# SmoothieDriver-DC3.net
KiCad netlist of a schematic drawn in EAGLE
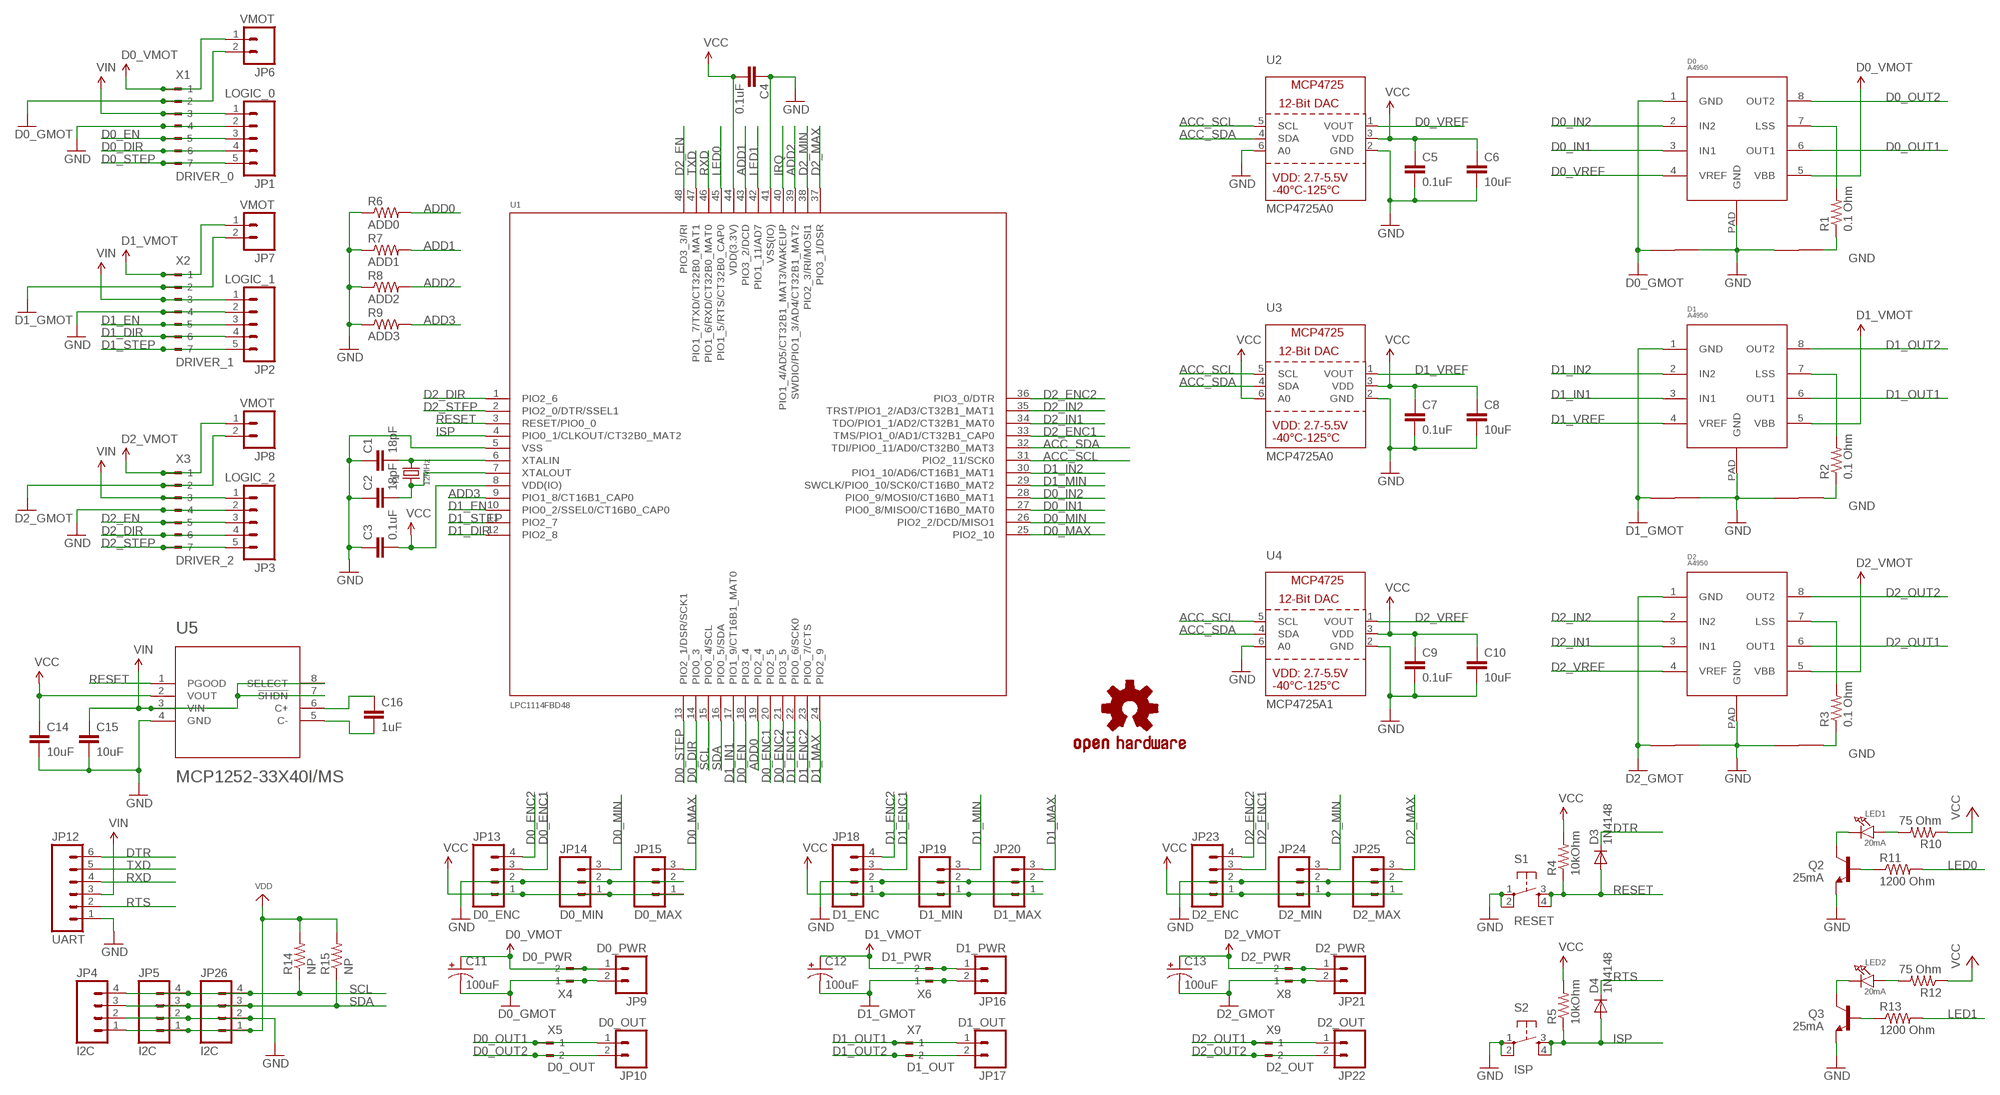
[diagram p0: schematic, sheet 1]

(export (version "E")
  (design (tool "Eeschema 10.0.6"))
  (components
    (comp (ref "C1")
      (value "18pF")
      (footprint "eagle-import:0603-CAP")
      (libsource (lib "eagle-import") (part "CAP0603-CAP"))
    )
    (comp (ref "C2")
      (value "18pF")
      (footprint "eagle-import:0603-CAP")
      (libsource (lib "eagle-import") (part "CAP0603-CAP"))
    )
    (comp (ref "C3")
      (value "0.1uF")
      (footprint "eagle-import:0603-CAP")
      (libsource (lib "eagle-import") (part "CAP0603-CAP"))
    )
    (comp (ref "C4")
      (value "0.1uF")
      (footprint "eagle-import:0603-CAP")
      (libsource (lib "eagle-import") (part "CAP0603-CAP"))
    )
    (comp (ref "C5")
      (value "0.1uF")
      (footprint "eagle-import:0603-CAP")
      (libsource (lib "eagle-import") (part "CAP0603-CAP"))
    )
    (comp (ref "C6")
      (value "10uF")
      (footprint "eagle-import:0603-CAP")
      (libsource (lib "eagle-import") (part "CAP0603-CAP"))
    )
    (comp (ref "C7")
      (value "0.1uF")
      (footprint "eagle-import:0603-CAP")
      (libsource (lib "eagle-import") (part "CAP0603-CAP"))
    )
    (comp (ref "C8")
      (value "10uF")
      (footprint "eagle-import:0603-CAP")
      (libsource (lib "eagle-import") (part "CAP0603-CAP"))
    )
    (comp (ref "C9")
      (value "0.1uF")
      (footprint "eagle-import:0603-CAP")
      (libsource (lib "eagle-import") (part "CAP0603-CAP"))
    )
    (comp (ref "C10")
      (value "10uF")
      (footprint "eagle-import:0603-CAP")
      (libsource (lib "eagle-import") (part "CAP0603-CAP"))
    )
    (comp (ref "C11")
      (value "100uF")
      (footprint "eagle-import:PANASONIC_E")
      (libsource (lib "eagle-import") (part "CAP_POLE"))
    )
    (comp (ref "C12")
      (value "100uF")
      (footprint "eagle-import:PANASONIC_E")
      (libsource (lib "eagle-import") (part "CAP_POLE"))
    )
    (comp (ref "C13")
      (value "100uF")
      (footprint "eagle-import:PANASONIC_E")
      (libsource (lib "eagle-import") (part "CAP_POLE"))
    )
    (comp (ref "C14")
      (value "10uF")
      (footprint "eagle-import:1206")
      (libsource (lib "eagle-import") (part "CAP1206"))
    )
    (comp (ref "C15")
      (value "10uF")
      (footprint "eagle-import:1206")
      (libsource (lib "eagle-import") (part "CAP1206"))
    )
    (comp (ref "C16")
      (value "1uF")
      (footprint "eagle-import:0805")
      (libsource (lib "eagle-import") (part "CAP0805"))
    )
    (comp (ref "D0")
      (value "A4950")
      (footprint "eagle-import:SOICN8-PAD")
      (libsource (lib "eagle-import") (part "A4950"))
    )
    (comp (ref "D0_GMOT")
      (value "NET_LINK")
      (footprint "eagle-import:NET_LINK")
      (libsource (lib "eagle-import") (part "NET_LINK"))
    )
    (comp (ref "D1")
      (value "A4950")
      (footprint "eagle-import:SOICN8-PAD")
      (libsource (lib "eagle-import") (part "A4950"))
    )
    (comp (ref "D2")
      (value "A4950")
      (footprint "eagle-import:SOICN8-PAD")
      (libsource (lib "eagle-import") (part "A4950"))
    )
    (comp (ref "D3")
      (value "1N4148")
      (footprint "eagle-import:SOD523")
      (libsource (lib "eagle-import") (part "DIODESOD523"))
    )
    (comp (ref "D4")
      (value "1N4148")
      (footprint "eagle-import:SOD523")
      (libsource (lib "eagle-import") (part "DIODESOD523"))
    )
    (comp (ref "JP1")
      (value "LOGIC_0")
      (footprint "eagle-import:1X05")
      (libsource (lib "eagle-import") (part "M05PTH"))
    )
    (comp (ref "JP2")
      (value "LOGIC_1")
      (footprint "eagle-import:1X05")
      (libsource (lib "eagle-import") (part "M05PTH"))
    )
    (comp (ref "JP3")
      (value "LOGIC_2")
      (footprint "eagle-import:1X05")
      (libsource (lib "eagle-import") (part "M05PTH"))
    )
    (comp (ref "JP4")
      (value "I2C")
      (footprint "eagle-import:1X04")
      (libsource (lib "eagle-import") (part "M04PTH"))
    )
    (comp (ref "JP5")
      (value "I2C")
      (footprint "eagle-import:1X04")
      (libsource (lib "eagle-import") (part "M04PTH"))
    )
    (comp (ref "JP6")
      (value "VMOT")
      (footprint "eagle-import:1X02")
      (libsource (lib "eagle-import") (part "M02PTH"))
    )
    (comp (ref "JP7")
      (value "VMOT")
      (footprint "eagle-import:1X02")
      (libsource (lib "eagle-import") (part "M02PTH"))
    )
    (comp (ref "JP8")
      (value "VMOT")
      (footprint "eagle-import:1X02")
      (libsource (lib "eagle-import") (part "M02PTH"))
    )
    (comp (ref "JP9")
      (value "D0_PWR")
      (footprint "eagle-import:1X02")
      (libsource (lib "eagle-import") (part "M02PTH"))
    )
    (comp (ref "JP10")
      (value "D0_OUT")
      (footprint "eagle-import:1X02")
      (libsource (lib "eagle-import") (part "M02PTH"))
    )
    (comp (ref "JP12")
      (value "UART")
      (footprint "eagle-import:1X06")
      (libsource (lib "eagle-import") (part "M06SIP"))
    )
    (comp (ref "JP13")
      (value "D0_ENC")
      (footprint "eagle-import:1X04")
      (libsource (lib "eagle-import") (part "M04PTH"))
    )
    (comp (ref "JP14")
      (value "D0_MIN")
      (footprint "eagle-import:1X03")
      (libsource (lib "eagle-import") (part "M03PTH"))
    )
    (comp (ref "JP15")
      (value "D0_MAX")
      (footprint "eagle-import:1X03")
      (libsource (lib "eagle-import") (part "M03PTH"))
    )
    (comp (ref "JP16")
      (value "D1_PWR")
      (footprint "eagle-import:1X02")
      (libsource (lib "eagle-import") (part "M02PTH"))
    )
    (comp (ref "JP17")
      (value "D1_OUT")
      (footprint "eagle-import:1X02")
      (libsource (lib "eagle-import") (part "M02PTH"))
    )
    (comp (ref "JP18")
      (value "D1_ENC")
      (footprint "eagle-import:1X04")
      (libsource (lib "eagle-import") (part "M04PTH"))
    )
    (comp (ref "JP19")
      (value "D1_MIN")
      (footprint "eagle-import:1X03")
      (libsource (lib "eagle-import") (part "M03PTH"))
    )
    (comp (ref "JP20")
      (value "D1_MAX")
      (footprint "eagle-import:1X03")
      (libsource (lib "eagle-import") (part "M03PTH"))
    )
    (comp (ref "JP21")
      (value "D2_PWR")
      (footprint "eagle-import:1X02")
      (libsource (lib "eagle-import") (part "M02PTH"))
    )
    (comp (ref "JP22")
      (value "D2_OUT")
      (footprint "eagle-import:1X02")
      (libsource (lib "eagle-import") (part "M02PTH"))
    )
    (comp (ref "JP23")
      (value "D2_ENC")
      (footprint "eagle-import:1X04")
      (libsource (lib "eagle-import") (part "M04PTH"))
    )
    (comp (ref "JP24")
      (value "D2_MIN")
      (footprint "eagle-import:1X03")
      (libsource (lib "eagle-import") (part "M03PTH"))
    )
    (comp (ref "JP25")
      (value "D2_MAX")
      (footprint "eagle-import:1X03")
      (libsource (lib "eagle-import") (part "M03PTH"))
    )
    (comp (ref "JP26")
      (value "I2C")
      (footprint "eagle-import:1X04")
      (libsource (lib "eagle-import") (part "M04PTH"))
    )
    (comp (ref "LED1")
      (value "20mA")
      (footprint "eagle-import:CHIPLED_0805")
      (libsource (lib "eagle-import") (part "LED0805"))
    )
    (comp (ref "LED2")
      (value "20mA")
      (footprint "eagle-import:CHIPLED_0805")
      (libsource (lib "eagle-import") (part "LED0805"))
    )
    (comp (ref "Q2")
      (value "25mA")
      (footprint "eagle-import:SOT23")
      (libsource (lib "eagle-import") (part "TRANSISTOR_NPNSOT23"))
    )
    (comp (ref "Q3")
      (value "25mA")
      (footprint "eagle-import:SOT23")
      (libsource (lib "eagle-import") (part "TRANSISTOR_NPNSOT23"))
    )
    (comp (ref "R1")
      (value "0.1 Ohm")
      (footprint "eagle-import:R2512")
      (libsource (lib "eagle-import") (part "RESISTOR2512"))
    )
    (comp (ref "R2")
      (value "0.1 Ohm")
      (footprint "eagle-import:R2512")
      (libsource (lib "eagle-import") (part "RESISTOR2512"))
    )
    (comp (ref "R3")
      (value "0.1 Ohm")
      (footprint "eagle-import:R2512")
      (libsource (lib "eagle-import") (part "RESISTOR2512"))
    )
    (comp (ref "R4")
      (value "10kOhm")
      (footprint "eagle-import:0603-RES")
      (libsource (lib "eagle-import") (part "RESISTOR0603-RES"))
    )
    (comp (ref "R5")
      (value "10kOhm")
      (footprint "eagle-import:0603-RES")
      (libsource (lib "eagle-import") (part "RESISTOR0603-RES"))
    )
    (comp (ref "R6")
      (value "ADD0")
      (footprint "eagle-import:0603-RES")
      (libsource (lib "eagle-import") (part "RESISTOR0603-RES"))
    )
    (comp (ref "R7")
      (value "ADD1")
      (footprint "eagle-import:0603-RES")
      (libsource (lib "eagle-import") (part "RESISTOR0603-RES"))
    )
    (comp (ref "R8")
      (value "ADD2")
      (footprint "eagle-import:0603-RES")
      (libsource (lib "eagle-import") (part "RESISTOR0603-RES"))
    )
    (comp (ref "R9")
      (value "ADD3")
      (footprint "eagle-import:0603-RES")
      (libsource (lib "eagle-import") (part "RESISTOR0603-RES"))
    )
    (comp (ref "R10")
      (value "75 Ohm")
      (footprint "eagle-import:R0603")
      (libsource (lib "eagle-import") (part "R-US_R0603"))
    )
    (comp (ref "R11")
      (value "1200 Ohm")
      (footprint "eagle-import:R0603")
      (libsource (lib "eagle-import") (part "R-US_R0603"))
    )
    (comp (ref "R12")
      (value "75 Ohm")
      (footprint "eagle-import:R0603")
      (libsource (lib "eagle-import") (part "R-US_R0603"))
    )
    (comp (ref "R13")
      (value "1200 Ohm")
      (footprint "eagle-import:R0603")
      (libsource (lib "eagle-import") (part "R-US_R0603"))
    )
    (comp (ref "R14")
      (value "NP")
      (footprint "eagle-import:0603-RES")
      (libsource (lib "eagle-import") (part "RESISTOR0603-RES"))
    )
    (comp (ref "R15")
      (value "NP")
      (footprint "eagle-import:0603-RES")
      (libsource (lib "eagle-import") (part "RESISTOR0603-RES"))
    )
    (comp (ref "S1")
      (value "RESET")
      (footprint "eagle-import:TACTILE_SWITCH_SMD")
      (libsource (lib "eagle-import") (part "TAC_SWITCHSMD"))
    )
    (comp (ref "S2")
      (value "ISP")
      (footprint "eagle-import:TACTILE_SWITCH_SMD")
      (libsource (lib "eagle-import") (part "TAC_SWITCHSMD"))
    )
    (comp (ref "U$15")
      (value "OSHW-LOGOM")
      (footprint "eagle-import:OSHW-LOGO-M")
      (libsource (lib "eagle-import") (part "OSHW-LOGOM"))
    )
    (comp (ref "U$22")
      (value "NET_LINK")
      (footprint "eagle-import:NET_LINK")
      (libsource (lib "eagle-import") (part "NET_LINK"))
    )
    (comp (ref "U$23")
      (value "NET_LINK")
      (footprint "eagle-import:NET_LINK")
      (libsource (lib "eagle-import") (part "NET_LINK"))
    )
    (comp (ref "U$24")
      (value "NET_LINK")
      (footprint "eagle-import:NET_LINK")
      (libsource (lib "eagle-import") (part "NET_LINK"))
    )
    (comp (ref "U$25")
      (value "NET_LINK")
      (footprint "eagle-import:NET_LINK")
      (libsource (lib "eagle-import") (part "NET_LINK"))
    )
    (comp (ref "U$26")
      (value "NET_LINK")
      (footprint "eagle-import:NET_LINK")
      (libsource (lib "eagle-import") (part "NET_LINK"))
    )
    (comp (ref "U1")
      (value "LPC1114FBD48")
      (footprint "eagle-import:LQFP48")
      (libsource (lib "eagle-import") (part "LPC1113/4_QFP_SQUARE"))
    )
    (comp (ref "U2")
      (value "MCP4725A0")
      (footprint "eagle-import:SOT23-6")
      (libsource (lib "eagle-import") (part "DAC_MCP4725"))
    )
    (comp (ref "U3")
      (value "MCP4725A0")
      (footprint "eagle-import:SOT23-6")
      (libsource (lib "eagle-import") (part "DAC_MCP4725"))
    )
    (comp (ref "U4")
      (value "MCP4725A1")
      (footprint "eagle-import:SOT23-6")
      (libsource (lib "eagle-import") (part "DAC_MCP4725"))
    )
    (comp (ref "U5")
      (value "MCP1252-33X40I/MS")
      (footprint "eagle-import:MSOP8_0.65MM")
      (libsource (lib "eagle-import") (part "MCP1253"))
    )
    (comp (ref "X1")
      (value "DRIVER_0")
      (footprint "eagle-import:180-7")
      (libsource (lib "eagle-import") (part "180-7"))
    )
    (comp (ref "X2")
      (value "DRIVER_1")
      (footprint "eagle-import:180-7")
      (libsource (lib "eagle-import") (part "180-7"))
    )
    (comp (ref "X3")
      (value "DRIVER_2")
      (footprint "eagle-import:180-7")
      (libsource (lib "eagle-import") (part "180-7"))
    )
    (comp (ref "X4")
      (value "D0_PWR")
      (footprint "eagle-import:180-2")
      (libsource (lib "eagle-import") (part "180-2"))
    )
    (comp (ref "X5")
      (value "D0_OUT")
      (footprint "eagle-import:180-2")
      (fields (field (name "OC_FARNELL") "unknown") (field (name "OC_NEWARK") "unknown"))
      (libsource (lib "eagle-import") (part "180-2"))
    )
    (comp (ref "X6")
      (value "D1_PWR")
      (footprint "eagle-import:180-2")
      (libsource (lib "eagle-import") (part "180-2"))
    )
    (comp (ref "X7")
      (value "D1_OUT")
      (footprint "eagle-import:180-2")
      (fields (field (name "OC_FARNELL") "unknown") (field (name "OC_NEWARK") "unknown"))
      (libsource (lib "eagle-import") (part "180-2"))
    )
    (comp (ref "X8")
      (value "D2_PWR")
      (footprint "eagle-import:180-2")
      (libsource (lib "eagle-import") (part "180-2"))
    )
    (comp (ref "X9")
      (value "D2_OUT")
      (footprint "eagle-import:180-2")
      (fields (field (name "OC_FARNELL") "unknown") (field (name "OC_NEWARK") "unknown"))
      (libsource (lib "eagle-import") (part "180-2"))
    )
    (comp (ref "Y1")
      (value "12MHz")
      (footprint "eagle-import:CRYSTAL_3.2X2.5")
      (libsource (lib "eagle-import") (part "CRYSTALTHIN"))
    )
  )
  (nets
    (net (code "1") (name "/ACC_SCL") (class "Default")
      (node (ref "U1") (pin "31") (pinfunction "PIO2_11/SCK0_31") (pintype "bidirectional"))
      (node (ref "U2") (pin "5") (pinfunction "SCL_5") (pintype "bidirectional"))
      (node (ref "U3") (pin "5") (pinfunction "SCL_5") (pintype "bidirectional"))
      (node (ref "U4") (pin "5") (pinfunction "SCL_5") (pintype "bidirectional"))
    )
    (net (code "2") (name "/ACC_SDA") (class "Default")
      (node (ref "U1") (pin "32") (pinfunction "TDI/PIO0_11/AD0/CT32B0_MAT3_32") (pintype "bidirectional"))
      (node (ref "U2") (pin "4") (pinfunction "SDA_4") (pintype "bidirectional"))
      (node (ref "U3") (pin "4") (pinfunction "SDA_4") (pintype "bidirectional"))
      (node (ref "U4") (pin "4") (pinfunction "SDA_4") (pintype "bidirectional"))
    )
    (net (code "3") (name "/ADD0") (class "Default")
      (node (ref "R6") (pin "2") (pinfunction "2_2") (pintype "passive"))
      (node (ref "U1") (pin "19") (pinfunction "PIO2_4_19") (pintype "bidirectional"))
    )
    (net (code "4") (name "/ADD1") (class "Default")
      (node (ref "R7") (pin "2") (pinfunction "2_2") (pintype "passive"))
      (node (ref "U1") (pin "43") (pinfunction "PIO3_2/DCD_43") (pintype "bidirectional"))
    )
    (net (code "5") (name "/ADD2") (class "Default")
      (node (ref "R8") (pin "2") (pinfunction "2_2") (pintype "passive"))
      (node (ref "U1") (pin "39") (pinfunction "SWDIO/PIO1_3/AD4/CT32B1_MAT2_39") (pintype "bidirectional"))
    )
    (net (code "6") (name "/ADD3") (class "Default")
      (node (ref "R9") (pin "2") (pinfunction "2_2") (pintype "passive"))
      (node (ref "U1") (pin "9") (pinfunction "PIO1_8/CT16B1_CAP0_9") (pintype "bidirectional"))
    )
    (net (code "7") (name "/D0_DIR") (class "Default")
      (node (ref "JP1") (pin "4") (pinfunction "4_4") (pintype "passive"))
      (node (ref "U1") (pin "14") (pinfunction "PIO0_3_14") (pintype "bidirectional"))
      (node (ref "X1") (pin "6") (pinfunction "6_6") (pintype "passive"))
    )
    (net (code "8") (name "/D0_EN") (class "Default")
      (node (ref "JP1") (pin "3") (pinfunction "3_3") (pintype "passive"))
      (node (ref "U1") (pin "18") (pinfunction "PIO3_4_18") (pintype "bidirectional"))
      (node (ref "X1") (pin "5") (pinfunction "5_5") (pintype "passive"))
    )
    (net (code "9") (name "/D0_ENC1") (class "Default")
      (node (ref "JP13") (pin "3") (pinfunction "3_3") (pintype "passive"))
      (node (ref "U1") (pin "20") (pinfunction "PIO2_5_20") (pintype "bidirectional"))
    )
    (net (code "10") (name "/D0_ENC2") (class "Default")
      (node (ref "JP13") (pin "4") (pinfunction "4_4") (pintype "passive"))
      (node (ref "U1") (pin "21") (pinfunction "PIO3_5_21") (pintype "bidirectional"))
    )
    (net (code "11") (name "/D0_IN1") (class "Default")
      (node (ref "D0") (pin "3") (pinfunction "IN1_3") (pintype "bidirectional"))
      (node (ref "U1") (pin "27") (pinfunction "PIO0_8/MISO0/CT16B0_MAT0_27") (pintype "bidirectional"))
    )
    (net (code "12") (name "/D0_IN2") (class "Default")
      (node (ref "D0") (pin "2") (pinfunction "IN2_2") (pintype "bidirectional"))
      (node (ref "U1") (pin "28") (pinfunction "PIO0_9/MOSI0/CT16B0_MAT1_28") (pintype "bidirectional"))
    )
    (net (code "13") (name "/D0_MAX") (class "Default")
      (node (ref "JP15") (pin "3") (pinfunction "3_3") (pintype "passive"))
      (node (ref "U1") (pin "25") (pinfunction "PIO2_10_25") (pintype "bidirectional"))
    )
    (net (code "14") (name "/D0_MIN") (class "Default")
      (node (ref "JP14") (pin "3") (pinfunction "3_3") (pintype "passive"))
      (node (ref "U1") (pin "26") (pinfunction "PIO2_2/DCD/MISO1_26") (pintype "bidirectional"))
    )
    (net (code "15") (name "/D0_OUT1") (class "Default")
      (node (ref "D0") (pin "6") (pinfunction "OUT1_6") (pintype "bidirectional"))
      (node (ref "JP10") (pin "1") (pinfunction "1_1") (pintype "passive"))
      (node (ref "X5") (pin "1") (pinfunction "1_1") (pintype "passive"))
    )
    (net (code "16") (name "/D0_OUT2") (class "Default")
      (node (ref "D0") (pin "8") (pinfunction "OUT2_8") (pintype "bidirectional"))
      (node (ref "JP10") (pin "2") (pinfunction "2_2") (pintype "passive"))
      (node (ref "X5") (pin "2") (pinfunction "2_2") (pintype "passive"))
    )
    (net (code "17") (name "/D0_STEP") (class "Default")
      (node (ref "JP1") (pin "5") (pinfunction "5_5") (pintype "passive"))
      (node (ref "U1") (pin "13") (pinfunction "PIO2_1/DSR/SCK1_13") (pintype "bidirectional"))
      (node (ref "X1") (pin "7") (pinfunction "7_7") (pintype "passive"))
    )
    (net (code "18") (name "/D0_VREF") (class "Default")
      (node (ref "D0") (pin "4") (pinfunction "VREF_4") (pintype "bidirectional"))
      (node (ref "U2") (pin "1") (pinfunction "VOUT_1") (pintype "output"))
    )
    (net (code "19") (name "/D1_DIR") (class "Default")
      (node (ref "JP2") (pin "4") (pinfunction "4_4") (pintype "passive"))
      (node (ref "U1") (pin "12") (pinfunction "PIO2_8_12") (pintype "bidirectional"))
      (node (ref "X2") (pin "6") (pinfunction "6_6") (pintype "passive"))
    )
    (net (code "20") (name "/D1_EN") (class "Default")
      (node (ref "JP2") (pin "3") (pinfunction "3_3") (pintype "passive"))
      (node (ref "U1") (pin "10") (pinfunction "PIO0_2/SSEL0/CT16B0_CAP0_10") (pintype "bidirectional"))
      (node (ref "X2") (pin "5") (pinfunction "5_5") (pintype "passive"))
    )
    (net (code "21") (name "/D1_ENC1") (class "Default")
      (node (ref "JP18") (pin "3") (pinfunction "3_3") (pintype "passive"))
      (node (ref "U1") (pin "22") (pinfunction "PIO0_6/SCK0_22") (pintype "bidirectional"))
    )
    (net (code "22") (name "/D1_ENC2") (class "Default")
      (node (ref "JP18") (pin "4") (pinfunction "4_4") (pintype "passive"))
      (node (ref "U1") (pin "23") (pinfunction "PIO0_7/CTS_23") (pintype "bidirectional"))
    )
    (net (code "23") (name "/D1_IN1") (class "Default")
      (node (ref "D1") (pin "3") (pinfunction "IN1_3") (pintype "bidirectional"))
      (node (ref "U1") (pin "17") (pinfunction "PIO1_9/CT16B1_MAT0_17") (pintype "bidirectional"))
    )
    (net (code "24") (name "/D1_IN2") (class "Default")
      (node (ref "D1") (pin "2") (pinfunction "IN2_2") (pintype "bidirectional"))
      (node (ref "U1") (pin "30") (pinfunction "PIO1_10/AD6/CT16B1_MAT1_30") (pintype "bidirectional"))
    )
    (net (code "25") (name "/D1_MAX") (class "Default")
      (node (ref "JP20") (pin "3") (pinfunction "3_3") (pintype "passive"))
      (node (ref "U1") (pin "24") (pinfunction "PIO2_9_24") (pintype "bidirectional"))
    )
    (net (code "26") (name "/D1_MIN") (class "Default")
      (node (ref "JP19") (pin "3") (pinfunction "3_3") (pintype "passive"))
      (node (ref "U1") (pin "29") (pinfunction "SWCLK/PIO0_10/SCK0/CT16B0_MAT2_29") (pintype "bidirectional"))
    )
    (net (code "27") (name "/D1_OUT1") (class "Default")
      (node (ref "D1") (pin "6") (pinfunction "OUT1_6") (pintype "bidirectional"))
      (node (ref "JP17") (pin "1") (pinfunction "1_1") (pintype "passive"))
      (node (ref "X7") (pin "1") (pinfunction "1_1") (pintype "passive"))
    )
    (net (code "28") (name "/D1_OUT2") (class "Default")
      (node (ref "D1") (pin "8") (pinfunction "OUT2_8") (pintype "bidirectional"))
      (node (ref "JP17") (pin "2") (pinfunction "2_2") (pintype "passive"))
      (node (ref "X7") (pin "2") (pinfunction "2_2") (pintype "passive"))
    )
    (net (code "29") (name "/D1_STEP") (class "Default")
      (node (ref "JP2") (pin "5") (pinfunction "5_5") (pintype "passive"))
      (node (ref "U1") (pin "11") (pinfunction "PIO2_7_11") (pintype "bidirectional"))
      (node (ref "X2") (pin "7") (pinfunction "7_7") (pintype "passive"))
    )
    (net (code "30") (name "/D1_VREF") (class "Default")
      (node (ref "D1") (pin "4") (pinfunction "VREF_4") (pintype "bidirectional"))
      (node (ref "U3") (pin "1") (pinfunction "VOUT_1") (pintype "output"))
    )
    (net (code "31") (name "/D2_DIR") (class "Default")
      (node (ref "JP3") (pin "4") (pinfunction "4_4") (pintype "passive"))
      (node (ref "U1") (pin "1") (pinfunction "PIO2_6_1") (pintype "bidirectional"))
      (node (ref "X3") (pin "6") (pinfunction "6_6") (pintype "passive"))
    )
    (net (code "32") (name "/D2_EN") (class "Default")
      (node (ref "JP3") (pin "3") (pinfunction "3_3") (pintype "passive"))
      (node (ref "U1") (pin "48") (pinfunction "PIO3_3/RI_48") (pintype "bidirectional"))
      (node (ref "X3") (pin "5") (pinfunction "5_5") (pintype "passive"))
    )
    (net (code "33") (name "/D2_ENC1") (class "Default")
      (node (ref "JP23") (pin "3") (pinfunction "3_3") (pintype "passive"))
      (node (ref "U1") (pin "33") (pinfunction "TMS/PIO1_0/AD1/CT32B1_CAP0_33") (pintype "bidirectional"))
    )
    (net (code "34") (name "/D2_ENC2") (class "Default")
      (node (ref "JP23") (pin "4") (pinfunction "4_4") (pintype "passive"))
      (node (ref "U1") (pin "36") (pinfunction "PIO3_0/DTR_36") (pintype "bidirectional"))
    )
    (net (code "35") (name "/D2_IN1") (class "Default")
      (node (ref "D2") (pin "3") (pinfunction "IN1_3") (pintype "bidirectional"))
      (node (ref "U1") (pin "34") (pinfunction "TDO/PIO1_1/AD2/CT32B1_MAT0_34") (pintype "bidirectional"))
    )
    (net (code "36") (name "/D2_IN2") (class "Default")
      (node (ref "D2") (pin "2") (pinfunction "IN2_2") (pintype "bidirectional"))
      (node (ref "U1") (pin "35") (pinfunction "TRST/PIO1_2/AD3/CT32B1_MAT1_35") (pintype "bidirectional"))
    )
    (net (code "37") (name "/D2_MAX") (class "Default")
      (node (ref "JP25") (pin "3") (pinfunction "3_3") (pintype "passive"))
      (node (ref "U1") (pin "37") (pinfunction "PIO3_1/DSR_37") (pintype "bidirectional"))
    )
    (net (code "38") (name "/D2_MIN") (class "Default")
      (node (ref "JP24") (pin "3") (pinfunction "3_3") (pintype "passive"))
      (node (ref "U1") (pin "38") (pinfunction "PIO2_3/RI/MOSI1_38") (pintype "bidirectional"))
    )
    (net (code "39") (name "/D2_OUT1") (class "Default")
      (node (ref "D2") (pin "6") (pinfunction "OUT1_6") (pintype "bidirectional"))
      (node (ref "JP22") (pin "1") (pinfunction "1_1") (pintype "passive"))
      (node (ref "X9") (pin "1") (pinfunction "1_1") (pintype "passive"))
    )
    (net (code "40") (name "/D2_OUT2") (class "Default")
      (node (ref "D2") (pin "8") (pinfunction "OUT2_8") (pintype "bidirectional"))
      (node (ref "JP22") (pin "2") (pinfunction "2_2") (pintype "passive"))
      (node (ref "X9") (pin "2") (pinfunction "2_2") (pintype "passive"))
    )
    (net (code "41") (name "/D2_STEP") (class "Default")
      (node (ref "JP3") (pin "5") (pinfunction "5_5") (pintype "passive"))
      (node (ref "U1") (pin "2") (pinfunction "PIO2_0/DTR/SSEL1_2") (pintype "bidirectional"))
      (node (ref "X3") (pin "7") (pinfunction "7_7") (pintype "passive"))
    )
    (net (code "42") (name "/D2_VREF") (class "Default")
      (node (ref "D2") (pin "4") (pinfunction "VREF_4") (pintype "bidirectional"))
      (node (ref "U4") (pin "1") (pinfunction "VOUT_1") (pintype "output"))
    )
    (net (code "43") (name "/DTR") (class "Default")
      (node (ref "D3") (pin "C") (pinfunction "C_C") (pintype "passive"))
      (node (ref "JP12") (pin "6") (pinfunction "6_6") (pintype "passive"))
    )
    (net (code "44") (name "/IRQ") (class "Default")
      (node (ref "U1") (pin "40") (pinfunction "PIO1_4/AD5/CT32B1_MAT3/WAKEUP_40") (pintype "bidirectional"))
    )
    (net (code "45") (name "/ISP") (class "Default")
      (node (ref "D4") (pin "A") (pinfunction "A_A") (pintype "passive"))
      (node (ref "R5") (pin "1") (pinfunction "1_1") (pintype "passive"))
      (node (ref "S2") (pin "3") (pinfunction "3_3") (pintype "passive"))
      (node (ref "S2") (pin "4") (pinfunction "4_4") (pintype "passive"))
      (node (ref "U1") (pin "4") (pinfunction "PIO0_1/CLKOUT/CT32B0_MAT2_4") (pintype "bidirectional"))
    )
    (net (code "46") (name "/LED0") (class "Default")
      (node (ref "R11") (pin "2") (pinfunction "2_2") (pintype "passive"))
      (node (ref "U1") (pin "45") (pinfunction "PIO1_5/RTS/CT32B0_CAP0_45") (pintype "bidirectional"))
    )
    (net (code "47") (name "/LED1") (class "Default")
      (node (ref "R13") (pin "2") (pinfunction "2_2") (pintype "passive"))
      (node (ref "U1") (pin "42") (pinfunction "PIO1_11/AD7_42") (pintype "bidirectional"))
    )
    (net (code "48") (name "/RESET") (class "Default")
      (node (ref "D3") (pin "A") (pinfunction "A_A") (pintype "passive"))
      (node (ref "R4") (pin "1") (pinfunction "1_1") (pintype "passive"))
      (node (ref "S1") (pin "3") (pinfunction "3_3") (pintype "passive"))
      (node (ref "S1") (pin "4") (pinfunction "4_4") (pintype "passive"))
      (node (ref "U1") (pin "3") (pinfunction "RESET/PIO0_0_3") (pintype "bidirectional"))
      (node (ref "U5") (pin "1") (pinfunction "PGOOD_1") (pintype "bidirectional"))
    )
    (net (code "49") (name "/RTS") (class "Default")
      (node (ref "D4") (pin "C") (pinfunction "C_C") (pintype "passive"))
      (node (ref "JP12") (pin "2") (pinfunction "2_2") (pintype "passive"))
    )
    (net (code "50") (name "/RXD") (class "Default")
      (node (ref "JP12") (pin "4") (pinfunction "4_4") (pintype "passive"))
      (node (ref "U1") (pin "46") (pinfunction "PIO1_6/RXD/CT32B0_MAT0_46") (pintype "bidirectional"))
    )
    (net (code "51") (name "/SCL") (class "Default")
      (node (ref "JP26") (pin "4") (pinfunction "4_4") (pintype "passive"))
      (node (ref "JP4") (pin "4") (pinfunction "4_4") (pintype "passive"))
      (node (ref "JP5") (pin "4") (pinfunction "4_4") (pintype "passive"))
      (node (ref "R14") (pin "1") (pinfunction "1_1") (pintype "passive"))
      (node (ref "U1") (pin "15") (pinfunction "PIO0_4/SCL_15") (pintype "bidirectional"))
    )
    (net (code "52") (name "/SDA") (class "Default")
      (node (ref "JP26") (pin "3") (pinfunction "3_3") (pintype "passive"))
      (node (ref "JP4") (pin "3") (pinfunction "3_3") (pintype "passive"))
      (node (ref "JP5") (pin "3") (pinfunction "3_3") (pintype "passive"))
      (node (ref "R15") (pin "1") (pinfunction "1_1") (pintype "passive"))
      (node (ref "U1") (pin "16") (pinfunction "PIO0_5/SDA_16") (pintype "bidirectional"))
    )
    (net (code "53") (name "/TXD") (class "Default")
      (node (ref "JP12") (pin "5") (pinfunction "5_5") (pintype "passive"))
      (node (ref "U1") (pin "47") (pinfunction "PIO1_7/TXD/CT32B0_MAT1_47") (pintype "bidirectional"))
    )
    (net (code "54") (name "D0_GMOT") (class "Default")
      (node (ref "C11") (pin "-") (pinfunction "-_-") (pintype "passive"))
      (node (ref "D0") (pin "1") (pinfunction "GND_1") (pintype "bidirectional"))
      (node (ref "D0_GMOT") (pin "P$1") (pinfunction "P$1_P$1") (pintype "bidirectional"))
      (node (ref "JP6") (pin "2") (pinfunction "2_2") (pintype "passive"))
      (node (ref "JP9") (pin "2") (pinfunction "2_2") (pintype "passive"))
      (node (ref "X1") (pin "2") (pinfunction "2_2") (pintype "passive"))
      (node (ref "X4") (pin "1") (pinfunction "1_1") (pintype "passive"))
    )
    (net (code "55") (name "D0_VMOT") (class "Default")
      (node (ref "C11") (pin "+") (pinfunction "+_+") (pintype "passive"))
      (node (ref "D0") (pin "5") (pinfunction "VBB_5") (pintype "bidirectional"))
      (node (ref "JP6") (pin "1") (pinfunction "1_1") (pintype "passive"))
      (node (ref "JP9") (pin "1") (pinfunction "1_1") (pintype "passive"))
      (node (ref "X1") (pin "1") (pinfunction "1_1") (pintype "passive"))
      (node (ref "X4") (pin "2") (pinfunction "2_2") (pintype "passive"))
    )
    (net (code "56") (name "D1_GMOT") (class "Default")
      (node (ref "C12") (pin "-") (pinfunction "-_-") (pintype "passive"))
      (node (ref "D1") (pin "1") (pinfunction "GND_1") (pintype "bidirectional"))
      (node (ref "JP16") (pin "2") (pinfunction "2_2") (pintype "passive"))
      (node (ref "JP7") (pin "2") (pinfunction "2_2") (pintype "passive"))
      (node (ref "U$23") (pin "P$1") (pinfunction "P$1_P$1") (pintype "bidirectional"))
      (node (ref "X2") (pin "2") (pinfunction "2_2") (pintype "passive"))
      (node (ref "X6") (pin "1") (pinfunction "1_1") (pintype "passive"))
    )
    (net (code "57") (name "D1_VMOT") (class "Default")
      (node (ref "C12") (pin "+") (pinfunction "+_+") (pintype "passive"))
      (node (ref "D1") (pin "5") (pinfunction "VBB_5") (pintype "bidirectional"))
      (node (ref "JP16") (pin "1") (pinfunction "1_1") (pintype "passive"))
      (node (ref "JP7") (pin "1") (pinfunction "1_1") (pintype "passive"))
      (node (ref "X2") (pin "1") (pinfunction "1_1") (pintype "passive"))
      (node (ref "X6") (pin "2") (pinfunction "2_2") (pintype "passive"))
    )
    (net (code "58") (name "D2_GMOT") (class "Default")
      (node (ref "C13") (pin "-") (pinfunction "-_-") (pintype "passive"))
      (node (ref "D2") (pin "1") (pinfunction "GND_1") (pintype "bidirectional"))
      (node (ref "JP21") (pin "2") (pinfunction "2_2") (pintype "passive"))
      (node (ref "JP8") (pin "2") (pinfunction "2_2") (pintype "passive"))
      (node (ref "U$26") (pin "P$1") (pinfunction "P$1_P$1") (pintype "bidirectional"))
      (node (ref "X3") (pin "2") (pinfunction "2_2") (pintype "passive"))
      (node (ref "X8") (pin "1") (pinfunction "1_1") (pintype "passive"))
    )
    (net (code "59") (name "D2_VMOT") (class "Default")
      (node (ref "C13") (pin "+") (pinfunction "+_+") (pintype "passive"))
      (node (ref "D2") (pin "5") (pinfunction "VBB_5") (pintype "bidirectional"))
      (node (ref "JP21") (pin "1") (pinfunction "1_1") (pintype "passive"))
      (node (ref "JP8") (pin "1") (pinfunction "1_1") (pintype "passive"))
      (node (ref "X3") (pin "1") (pinfunction "1_1") (pintype "passive"))
      (node (ref "X8") (pin "2") (pinfunction "2_2") (pintype "passive"))
    )
    (net (code "60") (name "GND") (class "Default")
      (node (ref "C1") (pin "1") (pinfunction "1_1") (pintype "passive"))
      (node (ref "C10") (pin "2") (pinfunction "2_2") (pintype "passive"))
      (node (ref "C14") (pin "2") (pinfunction "2_2") (pintype "passive"))
      (node (ref "C15") (pin "2") (pinfunction "2_2") (pintype "passive"))
      (node (ref "C2") (pin "1") (pinfunction "1_1") (pintype "passive"))
      (node (ref "C3") (pin "1") (pinfunction "1_1") (pintype "passive"))
      (node (ref "C4") (pin "1") (pinfunction "1_1") (pintype "passive"))
      (node (ref "C5") (pin "2") (pinfunction "2_2") (pintype "passive"))
      (node (ref "C6") (pin "2") (pinfunction "2_2") (pintype "passive"))
      (node (ref "C7") (pin "2") (pinfunction "2_2") (pintype "passive"))
      (node (ref "C8") (pin "2") (pinfunction "2_2") (pintype "passive"))
      (node (ref "C9") (pin "2") (pinfunction "2_2") (pintype "passive"))
      (node (ref "D0") (pin "PAD") (pinfunction "GND_PAD") (pintype "bidirectional"))
      (node (ref "D0_GMOT") (pin "P$2") (pinfunction "P$2_P$2") (pintype "bidirectional"))
      (node (ref "D1") (pin "PAD") (pinfunction "GND_PAD") (pintype "bidirectional"))
      (node (ref "D2") (pin "PAD") (pinfunction "GND_PAD") (pintype "bidirectional"))
      (node (ref "JP1") (pin "2") (pinfunction "2_2") (pintype "passive"))
      (node (ref "JP12") (pin "1") (pinfunction "1_1") (pintype "passive"))
      (node (ref "JP13") (pin "2") (pinfunction "2_2") (pintype "passive"))
      (node (ref "JP14") (pin "2") (pinfunction "2_2") (pintype "passive"))
      (node (ref "JP15") (pin "2") (pinfunction "2_2") (pintype "passive"))
      (node (ref "JP18") (pin "2") (pinfunction "2_2") (pintype "passive"))
      (node (ref "JP19") (pin "2") (pinfunction "2_2") (pintype "passive"))
      (node (ref "JP2") (pin "2") (pinfunction "2_2") (pintype "passive"))
      (node (ref "JP20") (pin "2") (pinfunction "2_2") (pintype "passive"))
      (node (ref "JP23") (pin "2") (pinfunction "2_2") (pintype "passive"))
      (node (ref "JP24") (pin "2") (pinfunction "2_2") (pintype "passive"))
      (node (ref "JP25") (pin "2") (pinfunction "2_2") (pintype "passive"))
      (node (ref "JP26") (pin "2") (pinfunction "2_2") (pintype "passive"))
      (node (ref "JP3") (pin "2") (pinfunction "2_2") (pintype "passive"))
      (node (ref "JP4") (pin "2") (pinfunction "2_2") (pintype "passive"))
      (node (ref "JP5") (pin "2") (pinfunction "2_2") (pintype "passive"))
      (node (ref "Q2") (pin "2") (pinfunction "E_2") (pintype "passive"))
      (node (ref "Q3") (pin "2") (pinfunction "E_2") (pintype "passive"))
      (node (ref "R1") (pin "1") (pinfunction "1_1") (pintype "passive"))
      (node (ref "R2") (pin "1") (pinfunction "1_1") (pintype "passive"))
      (node (ref "R3") (pin "1") (pinfunction "1_1") (pintype "passive"))
      (node (ref "R6") (pin "1") (pinfunction "1_1") (pintype "passive"))
      (node (ref "R7") (pin "1") (pinfunction "1_1") (pintype "passive"))
      (node (ref "R8") (pin "1") (pinfunction "1_1") (pintype "passive"))
      (node (ref "R9") (pin "1") (pinfunction "1_1") (pintype "passive"))
      (node (ref "S1") (pin "1") (pinfunction "1_1") (pintype "passive"))
      (node (ref "S1") (pin "2") (pinfunction "2_2") (pintype "passive"))
      (node (ref "S2") (pin "1") (pinfunction "1_1") (pintype "passive"))
      (node (ref "S2") (pin "2") (pinfunction "2_2") (pintype "passive"))
      (node (ref "U$22") (pin "P$1") (pinfunction "P$1_P$1") (pintype "bidirectional"))
      (node (ref "U$22") (pin "P$2") (pinfunction "P$2_P$2") (pintype "bidirectional"))
      (node (ref "U$23") (pin "P$2") (pinfunction "P$2_P$2") (pintype "bidirectional"))
      (node (ref "U$24") (pin "P$1") (pinfunction "P$1_P$1") (pintype "bidirectional"))
      (node (ref "U$24") (pin "P$2") (pinfunction "P$2_P$2") (pintype "bidirectional"))
      (node (ref "U$25") (pin "P$1") (pinfunction "P$1_P$1") (pintype "bidirectional"))
      (node (ref "U$25") (pin "P$2") (pinfunction "P$2_P$2") (pintype "bidirectional"))
      (node (ref "U$26") (pin "P$2") (pinfunction "P$2_P$2") (pintype "bidirectional"))
      (node (ref "U1") (pin "41") (pinfunction "VSS(IO)_41") (pintype "power_in"))
      (node (ref "U1") (pin "5") (pinfunction "VSS_5") (pintype "power_in"))
      (node (ref "U2") (pin "2") (pinfunction "GND_2") (pintype "power_in"))
      (node (ref "U2") (pin "6") (pinfunction "A0_6") (pintype "input"))
      (node (ref "U3") (pin "2") (pinfunction "GND_2") (pintype "power_in"))
      (node (ref "U4") (pin "2") (pinfunction "GND_2") (pintype "power_in"))
      (node (ref "U4") (pin "6") (pinfunction "A0_6") (pintype "input"))
      (node (ref "U5") (pin "4") (pinfunction "GND_4") (pintype "bidirectional"))
      (node (ref "X1") (pin "4") (pinfunction "4_4") (pintype "passive"))
      (node (ref "X2") (pin "4") (pinfunction "4_4") (pintype "passive"))
      (node (ref "X3") (pin "4") (pinfunction "4_4") (pintype "passive"))
    )
    (net (code "61") (name "Net-(D0-LSS)") (class "Default")
      (node (ref "D0") (pin "7") (pinfunction "LSS_7") (pintype "bidirectional"))
      (node (ref "R1") (pin "2") (pinfunction "2_2") (pintype "passive"))
    )
    (net (code "62") (name "Net-(D1-LSS)") (class "Default")
      (node (ref "D1") (pin "7") (pinfunction "LSS_7") (pintype "bidirectional"))
      (node (ref "R2") (pin "2") (pinfunction "2_2") (pintype "passive"))
    )
    (net (code "63") (name "Net-(D2-LSS)") (class "Default")
      (node (ref "D2") (pin "7") (pinfunction "LSS_7") (pintype "bidirectional"))
      (node (ref "R3") (pin "2") (pinfunction "2_2") (pintype "passive"))
    )
    (net (code "64") (name "Net-(LED1-PadA)") (class "Default")
      (node (ref "LED1") (pin "A") (pinfunction "A_A") (pintype "passive"))
      (node (ref "R10") (pin "2") (pinfunction "2_2") (pintype "passive"))
    )
    (net (code "65") (name "Net-(LED2-PadA)") (class "Default")
      (node (ref "LED2") (pin "A") (pinfunction "A_A") (pintype "passive"))
      (node (ref "R12") (pin "2") (pinfunction "2_2") (pintype "passive"))
    )
    (net (code "66") (name "Net-(Q2-B)") (class "Default")
      (node (ref "Q2") (pin "1") (pinfunction "B_1") (pintype "passive"))
      (node (ref "R11") (pin "1") (pinfunction "1_1") (pintype "passive"))
    )
    (net (code "67") (name "Net-(Q2-C)") (class "Default")
      (node (ref "LED1") (pin "C") (pinfunction "C_C") (pintype "passive"))
      (node (ref "Q2") (pin "3") (pinfunction "C_3") (pintype "passive"))
    )
    (net (code "68") (name "Net-(Q3-B)") (class "Default")
      (node (ref "Q3") (pin "1") (pinfunction "B_1") (pintype "passive"))
      (node (ref "R13") (pin "1") (pinfunction "1_1") (pintype "passive"))
    )
    (net (code "69") (name "Net-(Q3-C)") (class "Default")
      (node (ref "LED2") (pin "C") (pinfunction "C_C") (pintype "passive"))
      (node (ref "Q3") (pin "3") (pinfunction "C_3") (pintype "passive"))
    )
    (net (code "70") (name "Net-(U1-XTALIN)") (class "Default")
      (node (ref "C1") (pin "2") (pinfunction "2_2") (pintype "passive"))
      (node (ref "U1") (pin "6") (pinfunction "XTALIN_6") (pintype "input"))
      (node (ref "Y1") (pin "2") (pinfunction "2_2") (pintype "passive"))
    )
    (net (code "71") (name "Net-(U1-XTALOUT)") (class "Default")
      (node (ref "C2") (pin "2") (pinfunction "2_2") (pintype "passive"))
      (node (ref "U1") (pin "7") (pinfunction "XTALOUT_7") (pintype "output"))
      (node (ref "Y1") (pin "1") (pinfunction "1_1") (pintype "passive"))
    )
    (net (code "72") (name "Net-(U5-C+)") (class "Default")
      (node (ref "C16") (pin "1") (pinfunction "1_1") (pintype "passive"))
      (node (ref "U5") (pin "6") (pinfunction "C+_6") (pintype "bidirectional"))
    )
    (net (code "73") (name "Net-(U5-C-)") (class "Default")
      (node (ref "C16") (pin "2") (pinfunction "2_2") (pintype "passive"))
      (node (ref "U5") (pin "5") (pinfunction "C-_5") (pintype "bidirectional"))
    )
    (net (code "74") (name "VCC") (class "Default")
      (node (ref "C10") (pin "1") (pinfunction "1_1") (pintype "passive"))
      (node (ref "C14") (pin "1") (pinfunction "1_1") (pintype "passive"))
      (node (ref "C3") (pin "2") (pinfunction "2_2") (pintype "passive"))
      (node (ref "C4") (pin "2") (pinfunction "2_2") (pintype "passive"))
      (node (ref "C5") (pin "1") (pinfunction "1_1") (pintype "passive"))
      (node (ref "C6") (pin "1") (pinfunction "1_1") (pintype "passive"))
      (node (ref "C7") (pin "1") (pinfunction "1_1") (pintype "passive"))
      (node (ref "C8") (pin "1") (pinfunction "1_1") (pintype "passive"))
      (node (ref "C9") (pin "1") (pinfunction "1_1") (pintype "passive"))
      (node (ref "JP13") (pin "1") (pinfunction "1_1") (pintype "passive"))
      (node (ref "JP14") (pin "1") (pinfunction "1_1") (pintype "passive"))
      (node (ref "JP15") (pin "1") (pinfunction "1_1") (pintype "passive"))
      (node (ref "JP18") (pin "1") (pinfunction "1_1") (pintype "passive"))
      (node (ref "JP19") (pin "1") (pinfunction "1_1") (pintype "passive"))
      (node (ref "JP20") (pin "1") (pinfunction "1_1") (pintype "passive"))
      (node (ref "JP23") (pin "1") (pinfunction "1_1") (pintype "passive"))
      (node (ref "JP24") (pin "1") (pinfunction "1_1") (pintype "passive"))
      (node (ref "JP25") (pin "1") (pinfunction "1_1") (pintype "passive"))
      (node (ref "R10") (pin "1") (pinfunction "1_1") (pintype "passive"))
      (node (ref "R12") (pin "1") (pinfunction "1_1") (pintype "passive"))
      (node (ref "R4") (pin "2") (pinfunction "2_2") (pintype "passive"))
      (node (ref "R5") (pin "2") (pinfunction "2_2") (pintype "passive"))
      (node (ref "U1") (pin "44") (pinfunction "VDD(3.3V)_44") (pintype "power_in"))
      (node (ref "U1") (pin "8") (pinfunction "VDD(IO)_8") (pintype "power_in"))
      (node (ref "U2") (pin "3") (pinfunction "VDD_3") (pintype "power_in"))
      (node (ref "U3") (pin "3") (pinfunction "VDD_3") (pintype "power_in"))
      (node (ref "U3") (pin "6") (pinfunction "A0_6") (pintype "input"))
      (node (ref "U4") (pin "3") (pinfunction "VDD_3") (pintype "power_in"))
      (node (ref "U5") (pin "2") (pinfunction "VOUT_2") (pintype "bidirectional"))
    )
    (net (code "75") (name "VDD") (class "Default")
      (node (ref "JP26") (pin "1") (pinfunction "1_1") (pintype "passive"))
      (node (ref "JP4") (pin "1") (pinfunction "1_1") (pintype "passive"))
      (node (ref "JP5") (pin "1") (pinfunction "1_1") (pintype "passive"))
      (node (ref "R14") (pin "2") (pinfunction "2_2") (pintype "passive"))
      (node (ref "R15") (pin "2") (pinfunction "2_2") (pintype "passive"))
    )
    (net (code "76") (name "VIN") (class "Default")
      (node (ref "C15") (pin "1") (pinfunction "1_1") (pintype "passive"))
      (node (ref "JP1") (pin "1") (pinfunction "1_1") (pintype "passive"))
      (node (ref "JP12") (pin "3") (pinfunction "3_3") (pintype "passive"))
      (node (ref "JP2") (pin "1") (pinfunction "1_1") (pintype "passive"))
      (node (ref "JP3") (pin "1") (pinfunction "1_1") (pintype "passive"))
      (node (ref "U5") (pin "3") (pinfunction "VIN_3") (pintype "bidirectional"))
      (node (ref "U5") (pin "7") (pinfunction "~{SHDN}_7") (pintype "bidirectional"))
      (node (ref "U5") (pin "8") (pinfunction "SELECT_8") (pintype "bidirectional"))
      (node (ref "X1") (pin "3") (pinfunction "3_3") (pintype "passive"))
      (node (ref "X2") (pin "3") (pinfunction "3_3") (pintype "passive"))
      (node (ref "X3") (pin "3") (pinfunction "3_3") (pintype "passive"))
    )
  )
)
